# SAMV71.net
KiCad netlist of a schematic drawn in Altium Designer
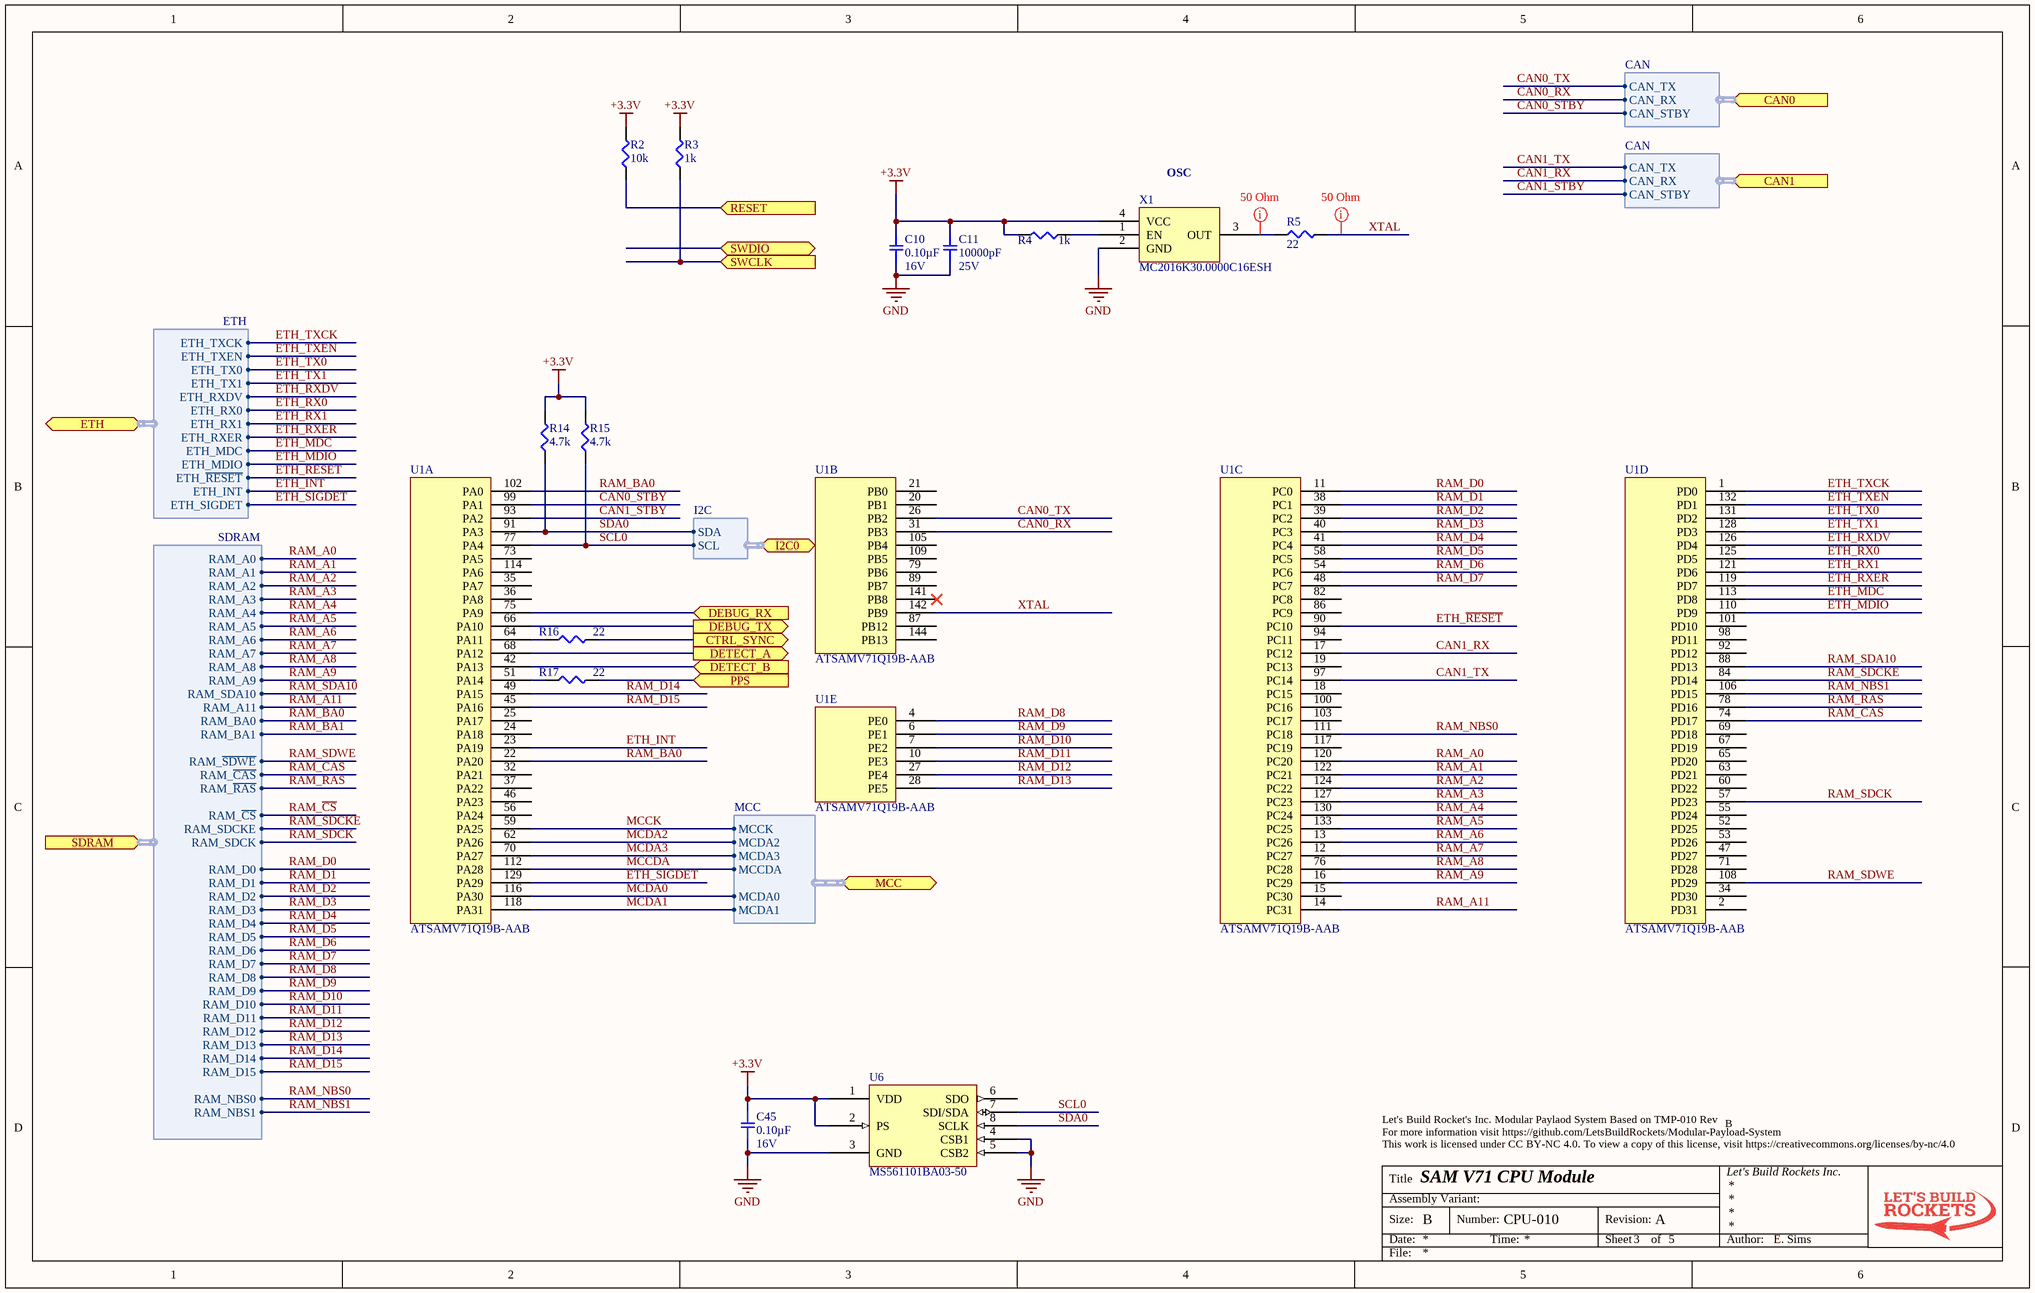
[diagram p0: SAMV71.SchDoc]

(export (version "E")
  (design (tool "Eeschema 10.0.6"))
  (components
    (comp (ref "C10")
      (value "0.10µF")
      (footprint "SMD-0402C")
      (description "CAP CER 0.1UF 16V X7R 0402")
      (fields
        (field (name "DIGI-KEY PART NUMBER") "490-4759-1-ND")
        (field (name "PART NUMBER") "GCM155R71C104KA55D")
        (field (name "VOLTAGE") "16V")
      )
      (libsource (lib "capacitor_murata_0402") (part "GCM155R71C104KA55D"))
    )
    (comp (ref "C11")
      (value "10000pF")
      (footprint "SMD-0402C")
      (description "CAP CER 10000PF 25V X7R 0402")
      (fields
        (field (name "DIGI-KEY PART NUMBER") "490-6043-1-ND")
        (field (name "PART NUMBER") "GCM155R71E103KA37D")
        (field (name "VOLTAGE") "25V")
      )
      (libsource (lib "capacitor_murata_0402") (part "GCM155R71E103KA37D"))
    )
    (comp (ref "C45")
      (value "0.10µF")
      (footprint "SMD-0402C")
      (description "CAP CER 0.1UF 16V X7R 0402")
      (fields
        (field (name "DIGI-KEY PART NUMBER") "490-4759-1-ND")
        (field (name "PART NUMBER") "GCM155R71C104KA55D")
        (field (name "VOLTAGE") "16V")
      )
      (libsource (lib "capacitor_murata_0402") (part "GCM155R71C104KA55D"))
    )
    (comp (ref "R2")
      (value "10k")
      (footprint "SMD-0402-RES")
      (description "RES SMD 10K OHM 5% 1/10W 0402")
      (fields (field (name "PART NUMBER") "ERJ-2GEJ103X") (field (name "DIGI-KEY PART NUMBER") "P10KJCT-ND"))
      (libsource (lib "Panasonic_ERJ_0402") (part "ERJ-2GEJ103X"))
    )
    (comp (ref "R3")
      (value "1k")
      (footprint "SMD-0402-RES")
      (description "RES SMD 1K OHM 5% 1/10W 0402")
      (fields (field (name "PART NUMBER") "ERJ-2GEJ102X") (field (name "DIGI-KEY PART NUMBER") "P1.0KJCT-ND"))
      (libsource (lib "Panasonic_ERJ_0402") (part "ERJ-2GEJ102X"))
    )
    (comp (ref "R4")
      (value "1k")
      (footprint "SMD-0402-RES")
      (description "RES SMD 1K OHM 5% 1/10W 0402")
      (fields (field (name "PART NUMBER") "ERJ-2GEJ102X") (field (name "DIGI-KEY PART NUMBER") "P1.0KJCT-ND"))
      (libsource (lib "Panasonic_ERJ_0402") (part "ERJ-2GEJ102X"))
    )
    (comp (ref "R5")
      (value "22")
      (footprint "SMD-0402-RES")
      (description "RES SMD 22 OHM 1% 1/10W 0402")
      (fields
        (field (name "PART NUMBER") "ERJ-2RKF22R0X")
        (field (name "DIGI-KEY PART NUMBER") "P22.0LCT-ND")
      )
      (libsource (lib "Panasonic_ERJ_0402") (part "ERJ-2RKF22R0X"))
    )
    (comp (ref "R14")
      (value "4.7k")
      (footprint "SMD-0402-RES")
      (description "RES SMD 4.7K OHM 5% 1/10W 0402")
      (fields (field (name "PART NUMBER") "ERJ-2GEJ472X") (field (name "DIGI-KEY PART NUMBER") "P4.7KJCT-ND"))
      (libsource (lib "Panasonic_ERJ_0402") (part "ERJ-2GEJ472X"))
    )
    (comp (ref "R15")
      (value "4.7k")
      (footprint "SMD-0402-RES")
      (description "RES SMD 4.7K OHM 5% 1/10W 0402")
      (fields (field (name "PART NUMBER") "ERJ-2GEJ472X") (field (name "DIGI-KEY PART NUMBER") "P4.7KJCT-ND"))
      (libsource (lib "Panasonic_ERJ_0402") (part "ERJ-2GEJ472X"))
    )
    (comp (ref "R16")
      (value "22")
      (footprint "SMD-0402-RES")
      (description "RES SMD 22 OHM 1% 1/10W 0402")
      (fields
        (field (name "PART NUMBER") "ERJ-2RKF22R0X")
        (field (name "DIGI-KEY PART NUMBER") "P22.0LCT-ND")
      )
      (libsource (lib "Panasonic_ERJ_0402") (part "ERJ-2RKF22R0X"))
    )
    (comp (ref "R17")
      (value "22")
      (footprint "SMD-0402-RES")
      (description "RES SMD 22 OHM 1% 1/10W 0402")
      (fields
        (field (name "PART NUMBER") "ERJ-2RKF22R0X")
        (field (name "DIGI-KEY PART NUMBER") "P22.0LCT-ND")
      )
      (libsource (lib "Panasonic_ERJ_0402") (part "ERJ-2RKF22R0X"))
    )
    (comp (ref "U1")
      (value "ATSAMV71Q19B-AAB")
      (footprint "TSQFP50P2200X2200X160-144N")
      (libsource (lib "ModularPayload") (part "ATSAMV71Q19B-AAB"))
    )
    (comp (ref "U6")
      (value "MS561101BA03-50")
      (footprint "MS561101BA03-50")
      (libsource (lib "ModularPayload") (part "MS561101BA03-50"))
    )
    (comp (ref "X1")
      (value "MC2016K30.0000C16ESH")
      (footprint "MC2016")
      (libsource (lib "ModularPayload") (part "MC2016K30.0000C16ESH"))
    )
  )
  (nets
    (net (code "6") (name "+3.3V") (class "Default")
      (node (ref "C10") (pin "2") (pinfunction "2_2") (pintype "passive"))
      (node (ref "C11") (pin "2") (pinfunction "2_2") (pintype "passive"))
      (node (ref "C45") (pin "2") (pinfunction "2_2") (pintype "passive"))
      (node (ref "R14") (pin "2") (pinfunction "2_2") (pintype "passive"))
      (node (ref "R15") (pin "2") (pinfunction "2_2") (pintype "passive"))
      (node (ref "R2") (pin "2") (pinfunction "2_2") (pintype "passive"))
      (node (ref "R3") (pin "2") (pinfunction "2_2") (pintype "passive"))
      (node (ref "R4") (pin "2") (pinfunction "2_2") (pintype "passive"))
      (node (ref "U6") (pin "1") (pinfunction "VDD_1") (pintype "power_in"))
      (node (ref "U6") (pin "2") (pinfunction "PS_2") (pintype "input"))
      (node (ref "X1") (pin "4") (pinfunction "VCC_4") (pintype "passive"))
    )
    (net (code "7") (name "/CAN0_RX") (class "Default")
      (node (ref "U1") (pin "31") (pinfunction "PB3_31") (pintype "passive"))
    )
    (net (code "8") (name "/CAN0_STBY") (class "Default")
      (node (ref "U1") (pin "99") (pinfunction "PA1_99") (pintype "passive"))
    )
    (net (code "9") (name "/CAN0_TX") (class "Default")
      (node (ref "U1") (pin "26") (pinfunction "PB2_26") (pintype "passive"))
    )
    (net (code "10") (name "/CAN1_RX") (class "Default")
      (node (ref "U1") (pin "17") (pinfunction "PC12_17") (pintype "passive"))
    )
    (net (code "11") (name "/CAN1_STBY") (class "Default")
      (node (ref "U1") (pin "93") (pinfunction "PA2_93") (pintype "passive"))
    )
    (net (code "12") (name "/CAN1_TX") (class "Default")
      (node (ref "U1") (pin "97") (pinfunction "PC14_97") (pintype "passive"))
    )
    (net (code "13") (name "/CTRL_SYNC") (class "Default")
      (node (ref "R16") (pin "2") (pinfunction "2_2") (pintype "passive"))
    )
    (net (code "14") (name "/DEBUG_RX") (class "Default")
      (node (ref "U1") (pin "75") (pinfunction "PA9_75") (pintype "passive"))
    )
    (net (code "15") (name "/DEBUG_TX") (class "Default")
      (node (ref "U1") (pin "66") (pinfunction "PA10_66") (pintype "passive"))
    )
    (net (code "16") (name "/DETECT_A") (class "Default")
      (node (ref "U1") (pin "68") (pinfunction "PA12_68") (pintype "passive"))
    )
    (net (code "17") (name "/DETECT_B") (class "Default")
      (node (ref "U1") (pin "42") (pinfunction "PA13_42") (pintype "passive"))
    )
    (net (code "18") (name "/ETH_INT") (class "Default")
      (node (ref "U1") (pin "23") (pinfunction "PA19_23") (pintype "passive"))
    )
    (net (code "19") (name "/ETH_MDC") (class "Default")
      (node (ref "U1") (pin "113") (pinfunction "PD8_113") (pintype "passive"))
    )
    (net (code "20") (name "/ETH_MDIO") (class "Default")
      (node (ref "U1") (pin "110") (pinfunction "PD9_110") (pintype "passive"))
    )
    (net (code "21") (name "/ETH_RX0") (class "Default")
      (node (ref "U1") (pin "125") (pinfunction "PD5_125") (pintype "passive"))
    )
    (net (code "22") (name "/ETH_RX1") (class "Default")
      (node (ref "U1") (pin "121") (pinfunction "PD6_121") (pintype "passive"))
    )
    (net (code "23") (name "/ETH_RXDV") (class "Default")
      (node (ref "U1") (pin "126") (pinfunction "PD4_126") (pintype "passive"))
    )
    (net (code "24") (name "/ETH_RXER") (class "Default")
      (node (ref "U1") (pin "119") (pinfunction "PD7_119") (pintype "passive"))
    )
    (net (code "25") (name "/ETH_SIGDET") (class "Default")
      (node (ref "U1") (pin "129") (pinfunction "PA29_129") (pintype "passive"))
    )
    (net (code "26") (name "/ETH_TX0") (class "Default")
      (node (ref "U1") (pin "131") (pinfunction "PD2_131") (pintype "passive"))
    )
    (net (code "27") (name "/ETH_TX1") (class "Default")
      (node (ref "U1") (pin "128") (pinfunction "PD3_128") (pintype "passive"))
    )
    (net (code "28") (name "/ETH_TXCK") (class "Default")
      (node (ref "U1") (pin "1") (pinfunction "PD0_1") (pintype "passive"))
    )
    (net (code "29") (name "/ETH_TXEN") (class "Default")
      (node (ref "U1") (pin "132") (pinfunction "PD1_132") (pintype "passive"))
    )
    (net (code "30") (name "/ETH_~{RESET}") (class "Default")
      (node (ref "U1") (pin "90") (pinfunction "PC10_90") (pintype "passive"))
    )
    (net (code "31") (name "/MCCDA") (class "Default")
      (node (ref "U1") (pin "112") (pinfunction "PA28_112") (pintype "passive"))
    )
    (net (code "32") (name "/MCCK") (class "Default")
      (node (ref "U1") (pin "59") (pinfunction "PA25_59") (pintype "passive"))
    )
    (net (code "33") (name "/MCDA0") (class "Default")
      (node (ref "U1") (pin "116") (pinfunction "PA30_116") (pintype "passive"))
    )
    (net (code "34") (name "/MCDA1") (class "Default")
      (node (ref "U1") (pin "118") (pinfunction "PA31_118") (pintype "passive"))
    )
    (net (code "35") (name "/MCDA2") (class "Default")
      (node (ref "U1") (pin "62") (pinfunction "PA26_62") (pintype "passive"))
    )
    (net (code "36") (name "/MCDA3") (class "Default")
      (node (ref "U1") (pin "70") (pinfunction "PA27_70") (pintype "passive"))
    )
    (net (code "37") (name "/PPS") (class "Default")
      (node (ref "R17") (pin "2") (pinfunction "2_2") (pintype "passive"))
    )
    (net (code "38") (name "/RAM_A0") (class "Default")
      (node (ref "U1") (pin "120") (pinfunction "PC20_120") (pintype "passive"))
    )
    (net (code "39") (name "/RAM_A1") (class "Default")
      (node (ref "U1") (pin "122") (pinfunction "PC21_122") (pintype "passive"))
    )
    (net (code "40") (name "/RAM_A2") (class "Default")
      (node (ref "U1") (pin "124") (pinfunction "PC22_124") (pintype "passive"))
    )
    (net (code "41") (name "/RAM_A3") (class "Default")
      (node (ref "U1") (pin "127") (pinfunction "PC23_127") (pintype "passive"))
    )
    (net (code "42") (name "/RAM_A4") (class "Default")
      (node (ref "U1") (pin "130") (pinfunction "PC24_130") (pintype "passive"))
    )
    (net (code "43") (name "/RAM_A5") (class "Default")
      (node (ref "U1") (pin "133") (pinfunction "PC25_133") (pintype "passive"))
    )
    (net (code "44") (name "/RAM_A6") (class "Default")
      (node (ref "U1") (pin "13") (pinfunction "PC26_13") (pintype "passive"))
    )
    (net (code "45") (name "/RAM_A7") (class "Default")
      (node (ref "U1") (pin "12") (pinfunction "PC27_12") (pintype "passive"))
    )
    (net (code "46") (name "/RAM_A8") (class "Default")
      (node (ref "U1") (pin "76") (pinfunction "PC28_76") (pintype "passive"))
    )
    (net (code "47") (name "/RAM_A9") (class "Default")
      (node (ref "U1") (pin "16") (pinfunction "PC29_16") (pintype "passive"))
    )
    (net (code "48") (name "/RAM_A11") (class "Default")
      (node (ref "U1") (pin "14") (pinfunction "PC31_14") (pintype "passive"))
    )
    (net (code "49") (name "/RAM_BA0") (class "Default")
      (node (ref "U1") (pin "102") (pinfunction "PA0_102") (pintype "passive"))
      (node (ref "U1") (pin "22") (pinfunction "PA20_22") (pintype "passive"))
    )
    (net (code "51") (name "/RAM_CAS") (class "Default")
      (node (ref "U1") (pin "74") (pinfunction "PD17_74") (pintype "passive"))
    )
    (net (code "52") (name "/RAM_D0") (class "Default")
      (node (ref "U1") (pin "11") (pinfunction "PC0_11") (pintype "passive"))
    )
    (net (code "53") (name "/RAM_D1") (class "Default")
      (node (ref "U1") (pin "38") (pinfunction "PC1_38") (pintype "passive"))
    )
    (net (code "54") (name "/RAM_D2") (class "Default")
      (node (ref "U1") (pin "39") (pinfunction "PC2_39") (pintype "passive"))
    )
    (net (code "55") (name "/RAM_D3") (class "Default")
      (node (ref "U1") (pin "40") (pinfunction "PC3_40") (pintype "passive"))
    )
    (net (code "56") (name "/RAM_D4") (class "Default")
      (node (ref "U1") (pin "41") (pinfunction "PC4_41") (pintype "passive"))
    )
    (net (code "57") (name "/RAM_D5") (class "Default")
      (node (ref "U1") (pin "58") (pinfunction "PC5_58") (pintype "passive"))
    )
    (net (code "58") (name "/RAM_D6") (class "Default")
      (node (ref "U1") (pin "54") (pinfunction "PC6_54") (pintype "passive"))
    )
    (net (code "59") (name "/RAM_D7") (class "Default")
      (node (ref "U1") (pin "48") (pinfunction "PC7_48") (pintype "passive"))
    )
    (net (code "60") (name "/RAM_D8") (class "Default")
      (node (ref "U1") (pin "4") (pinfunction "PE0_4") (pintype "passive"))
    )
    (net (code "61") (name "/RAM_D9") (class "Default")
      (node (ref "U1") (pin "6") (pinfunction "PE1_6") (pintype "passive"))
    )
    (net (code "62") (name "/RAM_D10") (class "Default")
      (node (ref "U1") (pin "7") (pinfunction "PE2_7") (pintype "passive"))
    )
    (net (code "63") (name "/RAM_D11") (class "Default")
      (node (ref "U1") (pin "10") (pinfunction "PE3_10") (pintype "passive"))
    )
    (net (code "64") (name "/RAM_D12") (class "Default")
      (node (ref "U1") (pin "27") (pinfunction "PE4_27") (pintype "passive"))
    )
    (net (code "65") (name "/RAM_D13") (class "Default")
      (node (ref "U1") (pin "28") (pinfunction "PE5_28") (pintype "passive"))
    )
    (net (code "66") (name "/RAM_D14") (class "Default")
      (node (ref "U1") (pin "49") (pinfunction "PA15_49") (pintype "passive"))
    )
    (net (code "67") (name "/RAM_D15") (class "Default")
      (node (ref "U1") (pin "45") (pinfunction "PA16_45") (pintype "passive"))
    )
    (net (code "68") (name "/RAM_NBS0") (class "Default")
      (node (ref "U1") (pin "111") (pinfunction "PC18_111") (pintype "passive"))
    )
    (net (code "69") (name "/RAM_NBS1") (class "Default")
      (node (ref "U1") (pin "106") (pinfunction "PD15_106") (pintype "passive"))
    )
    (net (code "70") (name "/RAM_RAS") (class "Default")
      (node (ref "U1") (pin "78") (pinfunction "PD16_78") (pintype "passive"))
    )
    (net (code "71") (name "/RAM_SDA10") (class "Default")
      (node (ref "U1") (pin "88") (pinfunction "PD13_88") (pintype "passive"))
    )
    (net (code "72") (name "/RAM_SDCK") (class "Default")
      (node (ref "U1") (pin "57") (pinfunction "PD23_57") (pintype "passive"))
    )
    (net (code "73") (name "/RAM_SDCKE") (class "Default")
      (node (ref "U1") (pin "84") (pinfunction "PD14_84") (pintype "passive"))
    )
    (net (code "74") (name "/RAM_SDWE") (class "Default")
      (node (ref "U1") (pin "108") (pinfunction "PD29_108") (pintype "passive"))
    )
    (net (code "76") (name "/RESET") (class "Default")
      (node (ref "R2") (pin "1") (pinfunction "1_1") (pintype "passive"))
    )
    (net (code "77") (name "/SCL0") (class "Default")
      (node (ref "R15") (pin "1") (pinfunction "1_1") (pintype "passive"))
      (node (ref "U1") (pin "77") (pinfunction "PA4_77") (pintype "passive"))
      (node (ref "U6") (pin "7") (pinfunction "SDI/SDA_7") (pintype "bidirectional"))
    )
    (net (code "78") (name "/SDA0") (class "Default")
      (node (ref "R14") (pin "1") (pinfunction "1_1") (pintype "passive"))
      (node (ref "U1") (pin "91") (pinfunction "PA3_91") (pintype "passive"))
      (node (ref "U6") (pin "8") (pinfunction "SCLK_8") (pintype "input"))
    )
    (net (code "79") (name "/SWCLK") (class "Default")
      (node (ref "R3") (pin "1") (pinfunction "1_1") (pintype "passive"))
    )
    (net (code "81") (name "/XTAL") (class "Default")
      (node (ref "R5") (pin "2") (pinfunction "2_2") (pintype "passive"))
      (node (ref "U1") (pin "142") (pinfunction "PB9_142") (pintype "passive"))
    )
    (net (code "87") (name "GND") (class "Default")
      (node (ref "C10") (pin "1") (pinfunction "1_1") (pintype "passive"))
      (node (ref "C11") (pin "1") (pinfunction "1_1") (pintype "passive"))
      (node (ref "C45") (pin "1") (pinfunction "1_1") (pintype "passive"))
      (node (ref "U6") (pin "3") (pinfunction "GND_3") (pintype "power_in"))
      (node (ref "U6") (pin "4") (pinfunction "CSB1_4") (pintype "input"))
      (node (ref "U6") (pin "5") (pinfunction "CSB2_5") (pintype "input"))
      (node (ref "X1") (pin "2") (pinfunction "GND_2") (pintype "passive"))
    )
    (net (code "88") (name "Net-(U1A-PA11)") (class "Default")
      (node (ref "R16") (pin "1") (pinfunction "1_1") (pintype "passive"))
      (node (ref "U1") (pin "64") (pinfunction "PA11_64") (pintype "passive"))
    )
    (net (code "89") (name "Net-(U1A-PA14)") (class "Default")
      (node (ref "R17") (pin "1") (pinfunction "1_1") (pintype "passive"))
      (node (ref "U1") (pin "51") (pinfunction "PA14_51") (pintype "passive"))
    )
    (net (code "90") (name "Net-(X1-EN)") (class "Default")
      (node (ref "R4") (pin "1") (pinfunction "1_1") (pintype "passive"))
      (node (ref "X1") (pin "1") (pinfunction "EN_1") (pintype "passive"))
    )
    (net (code "91") (name "Net-(X1-OUT)") (class "Default")
      (node (ref "R5") (pin "1") (pinfunction "1_1") (pintype "passive"))
      (node (ref "X1") (pin "3") (pinfunction "OUT_3") (pintype "passive"))
    )
    (net (code "92") (name "unconnected-(U1A-PA5-Pad73)") (class "Default")
      (node (ref "U1") (pin "73") (pinfunction "PA5_73") (pintype "passive"))
    )
    (net (code "93") (name "unconnected-(U1A-PA6-Pad114)") (class "Default")
      (node (ref "U1") (pin "114") (pinfunction "PA6_114") (pintype "passive"))
    )
    (net (code "94") (name "unconnected-(U1A-PA7-Pad35)") (class "Default")
      (node (ref "U1") (pin "35") (pinfunction "PA7_35") (pintype "passive"))
    )
    (net (code "95") (name "unconnected-(U1A-PA8-Pad36)") (class "Default")
      (node (ref "U1") (pin "36") (pinfunction "PA8_36") (pintype "passive"))
    )
    (net (code "96") (name "unconnected-(U1A-PA17-Pad25)") (class "Default")
      (node (ref "U1") (pin "25") (pinfunction "PA17_25") (pintype "passive"))
    )
    (net (code "97") (name "unconnected-(U1A-PA18-Pad24)") (class "Default")
      (node (ref "U1") (pin "24") (pinfunction "PA18_24") (pintype "passive"))
    )
    (net (code "98") (name "unconnected-(U1A-PA21-Pad32)") (class "Default")
      (node (ref "U1") (pin "32") (pinfunction "PA21_32") (pintype "passive"))
    )
    (net (code "99") (name "unconnected-(U1A-PA22-Pad37)") (class "Default")
      (node (ref "U1") (pin "37") (pinfunction "PA22_37") (pintype "passive"))
    )
    (net (code "100") (name "unconnected-(U1A-PA23-Pad46)") (class "Default")
      (node (ref "U1") (pin "46") (pinfunction "PA23_46") (pintype "passive"))
    )
    (net (code "101") (name "unconnected-(U1A-PA24-Pad56)") (class "Default")
      (node (ref "U1") (pin "56") (pinfunction "PA24_56") (pintype "passive"))
    )
    (net (code "102") (name "unconnected-(U1B-PB0-Pad21)") (class "Default")
      (node (ref "U1") (pin "21") (pinfunction "PB0_21") (pintype "passive"))
    )
    (net (code "103") (name "unconnected-(U1B-PB1-Pad20)") (class "Default")
      (node (ref "U1") (pin "20") (pinfunction "PB1_20") (pintype "passive"))
    )
    (net (code "104") (name "unconnected-(U1B-PB4-Pad105)") (class "Default")
      (node (ref "U1") (pin "105") (pinfunction "PB4_105") (pintype "passive"))
    )
    (net (code "105") (name "unconnected-(U1B-PB5-Pad109)") (class "Default")
      (node (ref "U1") (pin "109") (pinfunction "PB5_109") (pintype "passive"))
    )
    (net (code "106") (name "unconnected-(U1B-PB6-Pad79)") (class "Default")
      (node (ref "U1") (pin "79") (pinfunction "PB6_79") (pintype "passive"))
    )
    (net (code "107") (name "unconnected-(U1B-PB7-Pad89)") (class "Default")
      (node (ref "U1") (pin "89") (pinfunction "PB7_89") (pintype "passive"))
    )
    (net (code "108") (name "unconnected-(U1B-PB8-Pad141)") (class "Default")
      (node (ref "U1") (pin "141") (pinfunction "PB8_141") (pintype "passive+no_connect"))
    )
    (net (code "109") (name "unconnected-(U1B-PB12-Pad87)") (class "Default")
      (node (ref "U1") (pin "87") (pinfunction "PB12_87") (pintype "passive"))
    )
    (net (code "110") (name "unconnected-(U1B-PB13-Pad144)") (class "Default")
      (node (ref "U1") (pin "144") (pinfunction "PB13_144") (pintype "passive"))
    )
    (net (code "111") (name "unconnected-(U1C-PC8-Pad82)") (class "Default")
      (node (ref "U1") (pin "82") (pinfunction "PC8_82") (pintype "passive"))
    )
    (net (code "112") (name "unconnected-(U1C-PC9-Pad86)") (class "Default")
      (node (ref "U1") (pin "86") (pinfunction "PC9_86") (pintype "passive"))
    )
    (net (code "113") (name "unconnected-(U1C-PC11-Pad94)") (class "Default")
      (node (ref "U1") (pin "94") (pinfunction "PC11_94") (pintype "passive"))
    )
    (net (code "114") (name "unconnected-(U1C-PC13-Pad19)") (class "Default")
      (node (ref "U1") (pin "19") (pinfunction "PC13_19") (pintype "passive"))
    )
    (net (code "115") (name "unconnected-(U1C-PC15-Pad18)") (class "Default")
      (node (ref "U1") (pin "18") (pinfunction "PC15_18") (pintype "passive"))
    )
    (net (code "116") (name "unconnected-(U1C-PC16-Pad100)") (class "Default")
      (node (ref "U1") (pin "100") (pinfunction "PC16_100") (pintype "passive"))
    )
    (net (code "117") (name "unconnected-(U1C-PC17-Pad103)") (class "Default")
      (node (ref "U1") (pin "103") (pinfunction "PC17_103") (pintype "passive"))
    )
    (net (code "118") (name "unconnected-(U1C-PC19-Pad117)") (class "Default")
      (node (ref "U1") (pin "117") (pinfunction "PC19_117") (pintype "passive"))
    )
    (net (code "119") (name "unconnected-(U1C-PC30-Pad15)") (class "Default")
      (node (ref "U1") (pin "15") (pinfunction "PC30_15") (pintype "passive"))
    )
    (net (code "120") (name "unconnected-(U1D-PD10-Pad101)") (class "Default")
      (node (ref "U1") (pin "101") (pinfunction "PD10_101") (pintype "passive"))
    )
    (net (code "121") (name "unconnected-(U1D-PD11-Pad98)") (class "Default")
      (node (ref "U1") (pin "98") (pinfunction "PD11_98") (pintype "passive"))
    )
    (net (code "122") (name "unconnected-(U1D-PD12-Pad92)") (class "Default")
      (node (ref "U1") (pin "92") (pinfunction "PD12_92") (pintype "passive"))
    )
    (net (code "123") (name "unconnected-(U1D-PD18-Pad69)") (class "Default")
      (node (ref "U1") (pin "69") (pinfunction "PD18_69") (pintype "passive"))
    )
    (net (code "124") (name "unconnected-(U1D-PD19-Pad67)") (class "Default")
      (node (ref "U1") (pin "67") (pinfunction "PD19_67") (pintype "passive"))
    )
    (net (code "125") (name "unconnected-(U1D-PD20-Pad65)") (class "Default")
      (node (ref "U1") (pin "65") (pinfunction "PD20_65") (pintype "passive"))
    )
    (net (code "126") (name "unconnected-(U1D-PD21-Pad63)") (class "Default")
      (node (ref "U1") (pin "63") (pinfunction "PD21_63") (pintype "passive"))
    )
    (net (code "127") (name "unconnected-(U1D-PD22-Pad60)") (class "Default")
      (node (ref "U1") (pin "60") (pinfunction "PD22_60") (pintype "passive"))
    )
    (net (code "128") (name "unconnected-(U1D-PD24-Pad55)") (class "Default")
      (node (ref "U1") (pin "55") (pinfunction "PD24_55") (pintype "passive"))
    )
    (net (code "129") (name "unconnected-(U1D-PD25-Pad52)") (class "Default")
      (node (ref "U1") (pin "52") (pinfunction "PD25_52") (pintype "passive"))
    )
    (net (code "130") (name "unconnected-(U1D-PD26-Pad53)") (class "Default")
      (node (ref "U1") (pin "53") (pinfunction "PD26_53") (pintype "passive"))
    )
    (net (code "131") (name "unconnected-(U1D-PD27-Pad47)") (class "Default")
      (node (ref "U1") (pin "47") (pinfunction "PD27_47") (pintype "passive"))
    )
    (net (code "132") (name "unconnected-(U1D-PD28-Pad71)") (class "Default")
      (node (ref "U1") (pin "71") (pinfunction "PD28_71") (pintype "passive"))
    )
    (net (code "133") (name "unconnected-(U1D-PD30-Pad34)") (class "Default")
      (node (ref "U1") (pin "34") (pinfunction "PD30_34") (pintype "passive"))
    )
    (net (code "134") (name "unconnected-(U1D-PD31-Pad2)") (class "Default")
      (node (ref "U1") (pin "2") (pinfunction "PD31_2") (pintype "passive"))
    )
    (net (code "135") (name "unconnected-(U6-SDO-Pad6)") (class "Default")
      (node (ref "U6") (pin "6") (pinfunction "SDO_6") (pintype "output"))
    )
  )
)
